# FlukeNic_UNITB.net
KiCad netlist of a schematic drawn in EAGLE
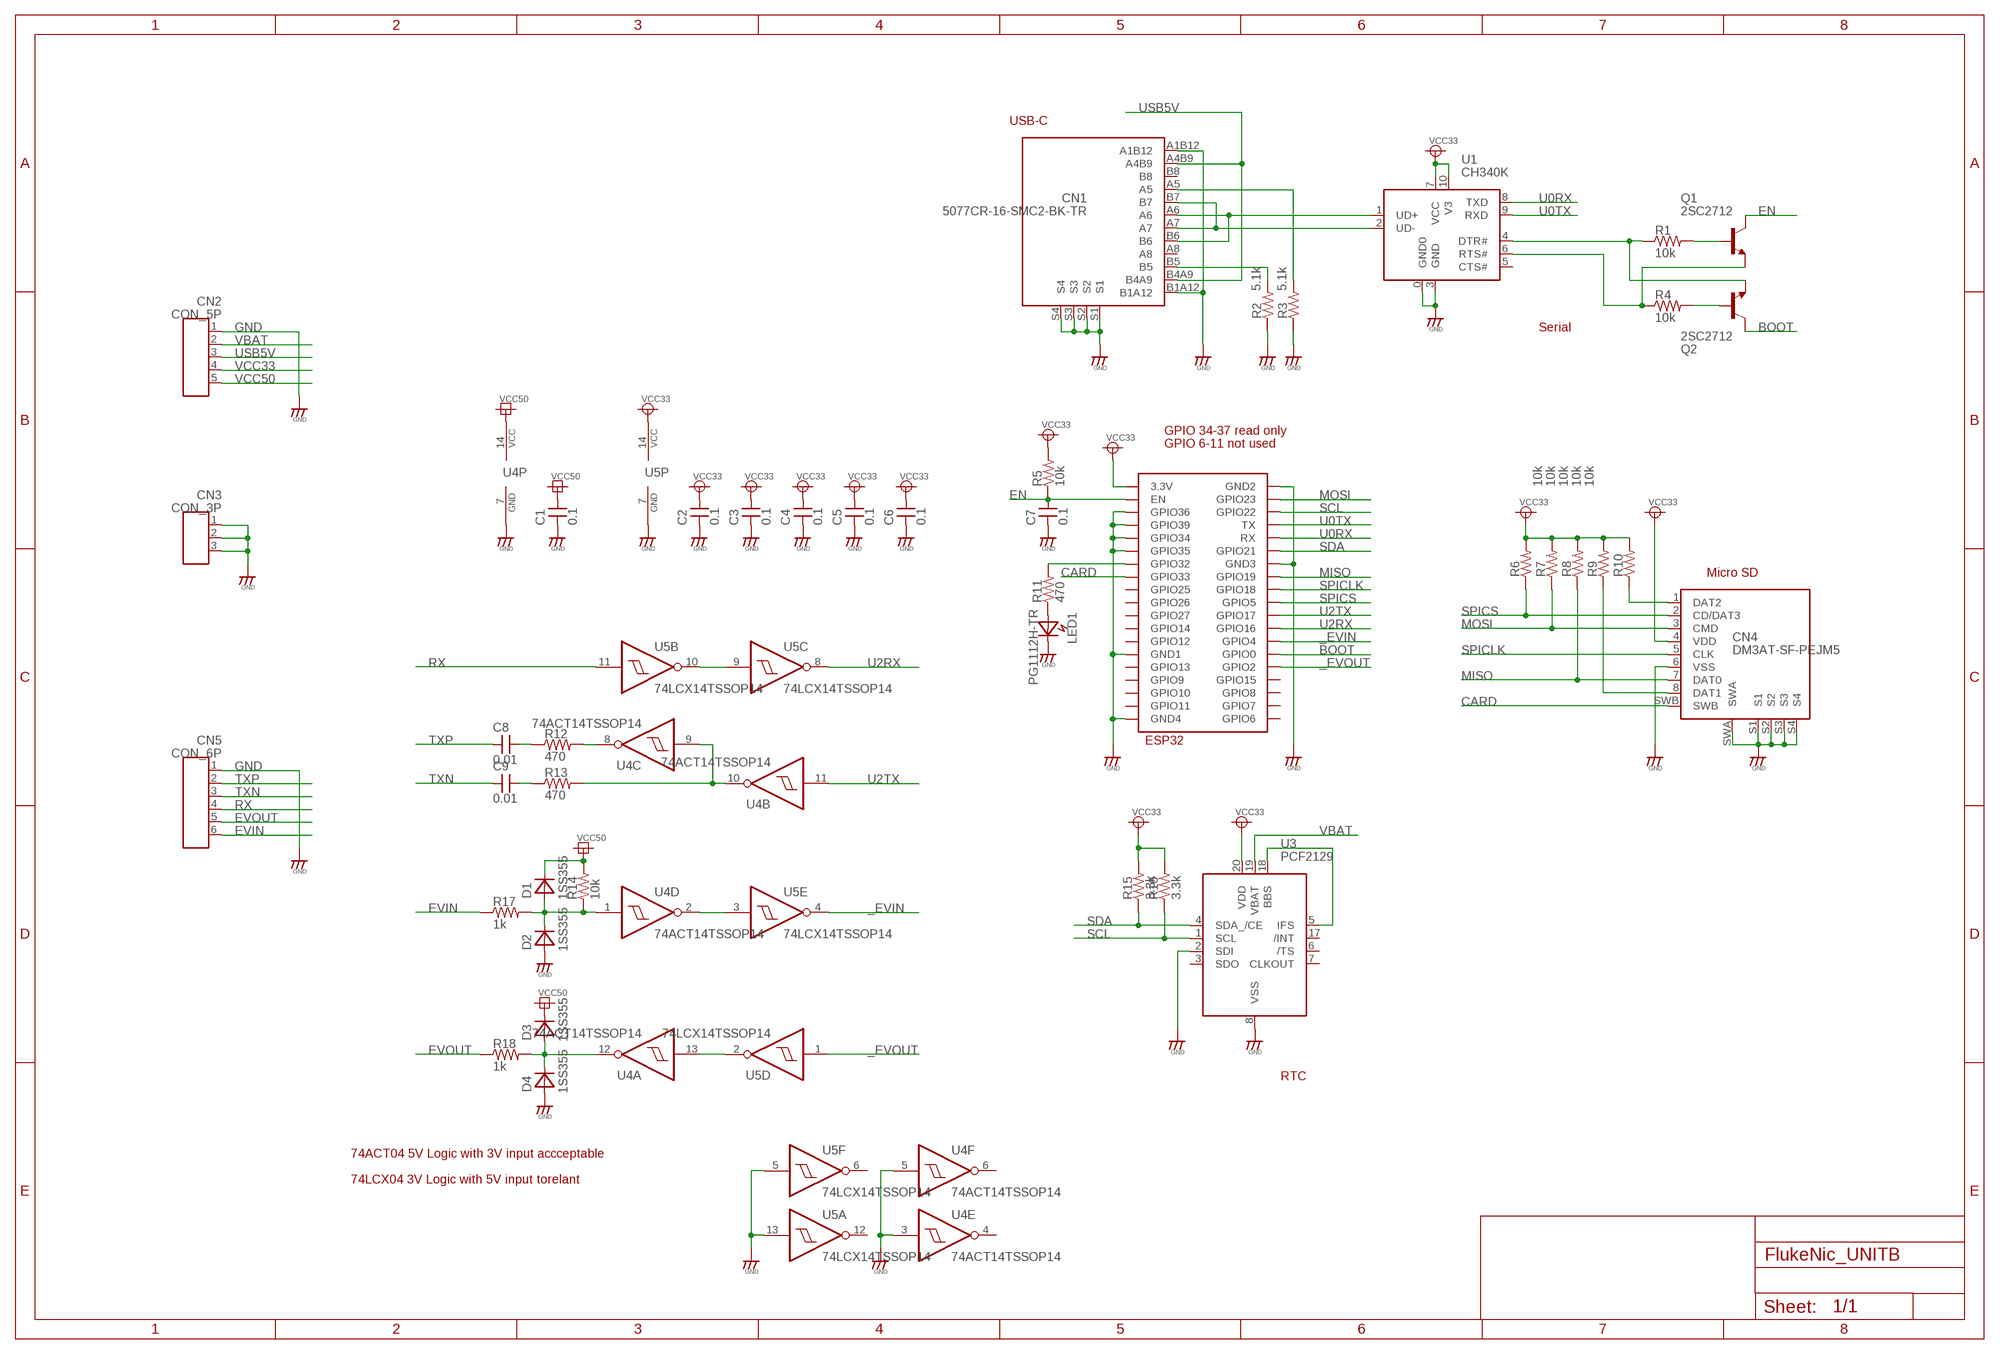
[diagram p0: schematic, sheet 1]

(export (version "E")
  (design (tool "Eeschema 10.0.6"))
  (components
    (comp (ref "C1")
      (value "0.1")
      (footprint "eagle-import:C2012")
      (libsource (lib "eagle-import") (part "CAPSM2012"))
    )
    (comp (ref "C2")
      (value "0.1")
      (footprint "eagle-import:C2012")
      (libsource (lib "eagle-import") (part "CAPSM2012"))
    )
    (comp (ref "C3")
      (value "0.1")
      (footprint "eagle-import:C2012")
      (libsource (lib "eagle-import") (part "CAPSM2012"))
    )
    (comp (ref "C4")
      (value "0.1")
      (footprint "eagle-import:C2012")
      (libsource (lib "eagle-import") (part "CAPSM2012"))
    )
    (comp (ref "C5")
      (value "0.1")
      (footprint "eagle-import:C2012")
      (libsource (lib "eagle-import") (part "CAPSM2012"))
    )
    (comp (ref "C6")
      (value "0.1")
      (footprint "eagle-import:C2012")
      (libsource (lib "eagle-import") (part "CAPSM2012"))
    )
    (comp (ref "C7")
      (value "0.1")
      (footprint "eagle-import:C2012")
      (libsource (lib "eagle-import") (part "CAPSM2012"))
    )
    (comp (ref "C8")
      (value "0.01")
      (footprint "eagle-import:C2012")
      (libsource (lib "eagle-import") (part "CAPSM2012"))
    )
    (comp (ref "C9")
      (value "0.01")
      (footprint "eagle-import:C2012")
      (libsource (lib "eagle-import") (part "CAPSM2012"))
    )
    (comp (ref "CN1")
      (value "5077CR-16-SMC2-BK-TR")
      (footprint "eagle-import:5077CR-16-SMC2-BK-TR")
      (libsource (lib "eagle-import") (part "5077CR-16-SMC2-BK-TR"))
    )
    (comp (ref "CN2")
      (value "CON_5P")
      (footprint "eagle-import:CON_HDR_SIP5")
      (libsource (lib "eagle-import") (part "CON_5P"))
    )
    (comp (ref "CN3")
      (value "CON_3P")
      (footprint "eagle-import:CON_HDR_SIP3")
      (libsource (lib "eagle-import") (part "CON_3P"))
    )
    (comp (ref "CN4")
      (value "DM3AT-SF-PEJM5")
      (footprint "eagle-import:DM3AT-SF-PEJM5")
      (libsource (lib "eagle-import") (part "DM3AT-SF-PEJM5"))
    )
    (comp (ref "CN5")
      (value "CON_6P")
      (footprint "eagle-import:CON_HDR_SIP6")
      (libsource (lib "eagle-import") (part "CON_6P"))
    )
    (comp (ref "D1")
      (value "1SS355")
      (footprint "eagle-import:SOD323")
      (libsource (lib "eagle-import") (part "DIODESOD323"))
    )
    (comp (ref "D2")
      (value "1SS355")
      (footprint "eagle-import:SOD323")
      (libsource (lib "eagle-import") (part "DIODESOD323"))
    )
    (comp (ref "D3")
      (value "1SS355")
      (footprint "eagle-import:SOD323")
      (libsource (lib "eagle-import") (part "DIODESOD323"))
    )
    (comp (ref "D4")
      (value "1SS355")
      (footprint "eagle-import:SOD323")
      (libsource (lib "eagle-import") (part "DIODESOD323"))
    )
    (comp (ref "LED1")
      (value "PG1112H-TR")
      (footprint "eagle-import:LED2125")
      (libsource (lib "eagle-import") (part "LED2125"))
    )
    (comp (ref "Q1")
      (value "2SC2712")
      (footprint "eagle-import:SC59")
      (libsource (lib "eagle-import") (part "2SC2712"))
    )
    (comp (ref "Q2")
      (value "2SC2712")
      (footprint "eagle-import:SC59")
      (libsource (lib "eagle-import") (part "2SC2712"))
    )
    (comp (ref "R1")
      (value "10k")
      (footprint "eagle-import:R2012")
      (libsource (lib "eagle-import") (part "RSMD2012"))
    )
    (comp (ref "R2")
      (value "5.1k")
      (footprint "eagle-import:R2012")
      (libsource (lib "eagle-import") (part "RSMD2012"))
    )
    (comp (ref "R3")
      (value "5.1k")
      (footprint "eagle-import:R2012")
      (libsource (lib "eagle-import") (part "RSMD2012"))
    )
    (comp (ref "R4")
      (value "10k")
      (footprint "eagle-import:R2012")
      (libsource (lib "eagle-import") (part "RSMD2012"))
    )
    (comp (ref "R5")
      (value "10k")
      (footprint "eagle-import:R2012")
      (libsource (lib "eagle-import") (part "RSMD2012"))
    )
    (comp (ref "R6")
      (value "10k")
      (footprint "eagle-import:R2012")
      (libsource (lib "eagle-import") (part "RSMD2012"))
    )
    (comp (ref "R7")
      (value "10k")
      (footprint "eagle-import:R2012")
      (libsource (lib "eagle-import") (part "RSMD2012"))
    )
    (comp (ref "R8")
      (value "10k")
      (footprint "eagle-import:R2012")
      (libsource (lib "eagle-import") (part "RSMD2012"))
    )
    (comp (ref "R9")
      (value "10k")
      (footprint "eagle-import:R2012")
      (libsource (lib "eagle-import") (part "RSMD2012"))
    )
    (comp (ref "R10")
      (value "10k")
      (footprint "eagle-import:R2012")
      (libsource (lib "eagle-import") (part "RSMD2012"))
    )
    (comp (ref "R11")
      (value "470")
      (footprint "eagle-import:R2012")
      (libsource (lib "eagle-import") (part "RSMD2012"))
    )
    (comp (ref "R12")
      (value "470")
      (footprint "eagle-import:R2012")
      (libsource (lib "eagle-import") (part "RSMD2012"))
    )
    (comp (ref "R13")
      (value "470")
      (footprint "eagle-import:R2012")
      (libsource (lib "eagle-import") (part "RSMD2012"))
    )
    (comp (ref "R14")
      (value "10k")
      (footprint "eagle-import:R2012")
      (libsource (lib "eagle-import") (part "RSMD2012"))
    )
    (comp (ref "R15")
      (value "3.3k")
      (footprint "eagle-import:R2012")
      (libsource (lib "eagle-import") (part "RSMD2012"))
    )
    (comp (ref "R16")
      (value "3.3k")
      (footprint "eagle-import:R2012")
      (libsource (lib "eagle-import") (part "RSMD2012"))
    )
    (comp (ref "R17")
      (value "1k")
      (footprint "eagle-import:R2012")
      (libsource (lib "eagle-import") (part "RSMD2012"))
    )
    (comp (ref "R18")
      (value "1k")
      (footprint "eagle-import:R2012")
      (libsource (lib "eagle-import") (part "RSMD2012"))
    )
    (comp (ref "U1")
      (value "CH340K")
      (footprint "eagle-import:ESSOP10")
      (libsource (lib "eagle-import") (part "CH340K"))
    )
    (comp (ref "U2")
      (value "ESP32-WROOM")
      (footprint "eagle-import:ESP32-WROOM")
      (libsource (lib "eagle-import") (part "ESP32-WROOM"))
    )
    (comp (ref "U3")
      (value "PCF2129")
      (footprint "eagle-import:SO20")
      (libsource (lib "eagle-import") (part "PCF2129"))
    )
    (comp (ref "U4")
      (value "74ACT14TSSOP14")
      (footprint "eagle-import:TSSOP14")
      (libsource (lib "eagle-import") (part "7414TSSOP14VHCT"))
    )
    (comp (ref "U5")
      (value "74LCX14TSSOP14")
      (footprint "eagle-import:TSSOP14")
      (libsource (lib "eagle-import") (part "7414TSSOP14LCX"))
    )
  )
  (nets
    (net (code "1") (name "/BOOT") (class "Default")
      (node (ref "Q2") (pin "C") (pinfunction "C_C") (pintype "passive"))
      (node (ref "U2") (pin "IO0") (pinfunction "GPIO0_IO0") (pintype "bidirectional"))
    )
    (net (code "2") (name "/CARD") (class "Default")
      (node (ref "CN4") (pin "SWB") (pinfunction "SWB_SWB") (pintype "passive"))
      (node (ref "U2") (pin "IO33") (pinfunction "GPIO33_IO33") (pintype "bidirectional"))
    )
    (net (code "3") (name "/EN") (class "Default")
      (node (ref "C7") (pin "2") (pinfunction "2_2") (pintype "passive"))
      (node (ref "Q1") (pin "C") (pinfunction "C_C") (pintype "passive"))
      (node (ref "R5") (pin "1") (pinfunction "1_1") (pintype "passive"))
      (node (ref "U2") (pin "EN") (pinfunction "EN_EN") (pintype "bidirectional"))
    )
    (net (code "4") (name "/EVIN") (class "Default")
      (node (ref "CN5") (pin "6") (pinfunction "6_6") (pintype "passive"))
      (node (ref "R17") (pin "1") (pinfunction "1_1") (pintype "passive"))
    )
    (net (code "5") (name "/EVOUT") (class "Default")
      (node (ref "CN5") (pin "5") (pinfunction "5_5") (pintype "passive"))
      (node (ref "R18") (pin "1") (pinfunction "1_1") (pintype "passive"))
    )
    (net (code "6") (name "/MISO") (class "Default")
      (node (ref "CN4") (pin "7") (pinfunction "DAT0_7") (pintype "bidirectional"))
      (node (ref "R8") (pin "1") (pinfunction "1_1") (pintype "passive"))
      (node (ref "U2") (pin "IO19") (pinfunction "GPIO19_IO19") (pintype "bidirectional"))
    )
    (net (code "7") (name "/MOSI") (class "Default")
      (node (ref "CN4") (pin "3") (pinfunction "CMD_3") (pintype "bidirectional"))
      (node (ref "R7") (pin "1") (pinfunction "1_1") (pintype "passive"))
      (node (ref "U2") (pin "IO23") (pinfunction "GPIO23_IO23") (pintype "bidirectional"))
    )
    (net (code "8") (name "/RX") (class "Default")
      (node (ref "CN5") (pin "4") (pinfunction "4_4") (pintype "passive"))
      (node (ref "U5") (pin "11") (pinfunction "I_11") (pintype "input"))
    )
    (net (code "9") (name "/SCL") (class "Default")
      (node (ref "R16") (pin "1") (pinfunction "1_1") (pintype "passive"))
      (node (ref "U2") (pin "IO22") (pinfunction "GPIO22_IO22") (pintype "bidirectional"))
      (node (ref "U3") (pin "1") (pinfunction "SCL_1") (pintype "input"))
    )
    (net (code "10") (name "/SDA") (class "Default")
      (node (ref "R15") (pin "1") (pinfunction "1_1") (pintype "passive"))
      (node (ref "U2") (pin "IO21") (pinfunction "GPIO21_IO21") (pintype "bidirectional"))
      (node (ref "U3") (pin "4") (pinfunction "SDA_/CE_4") (pintype "bidirectional"))
    )
    (net (code "11") (name "/SPICLK") (class "Default")
      (node (ref "CN4") (pin "5") (pinfunction "CLK_5") (pintype "input"))
      (node (ref "U2") (pin "IO18") (pinfunction "GPIO18_IO18") (pintype "bidirectional"))
    )
    (net (code "12") (name "/SPICS") (class "Default")
      (node (ref "CN4") (pin "2") (pinfunction "CD/DAT3_2") (pintype "bidirectional"))
      (node (ref "R6") (pin "1") (pinfunction "1_1") (pintype "passive"))
      (node (ref "U2") (pin "IO5") (pinfunction "GPIO5_IO5") (pintype "bidirectional"))
    )
    (net (code "13") (name "/TXN") (class "Default")
      (node (ref "C9") (pin "1") (pinfunction "1_1") (pintype "passive"))
      (node (ref "CN5") (pin "3") (pinfunction "3_3") (pintype "passive"))
    )
    (net (code "14") (name "/TXP") (class "Default")
      (node (ref "C8") (pin "1") (pinfunction "1_1") (pintype "passive"))
      (node (ref "CN5") (pin "2") (pinfunction "2_2") (pintype "passive"))
    )
    (net (code "15") (name "/U0RX") (class "Default")
      (node (ref "U1") (pin "8") (pinfunction "TXD_8") (pintype "output"))
      (node (ref "U2") (pin "RX") (pinfunction "RX_RX") (pintype "bidirectional"))
    )
    (net (code "16") (name "/U0TX") (class "Default")
      (node (ref "U1") (pin "9") (pinfunction "RXD_9") (pintype "input"))
      (node (ref "U2") (pin "TX") (pinfunction "TX_TX") (pintype "bidirectional"))
    )
    (net (code "17") (name "/U2RX") (class "Default")
      (node (ref "U2") (pin "IO16") (pinfunction "GPIO16_IO16") (pintype "bidirectional"))
      (node (ref "U5") (pin "8") (pinfunction "O_8") (pintype "output"))
    )
    (net (code "18") (name "/U2TX") (class "Default")
      (node (ref "U2") (pin "IO17") (pinfunction "GPIO17_IO17") (pintype "bidirectional"))
      (node (ref "U4") (pin "11") (pinfunction "I_11") (pintype "input"))
    )
    (net (code "19") (name "/USB5V") (class "Default")
      (node (ref "CN1") (pin "A4B9") (pinfunction "A4B9_A4B9") (pintype "bidirectional"))
      (node (ref "CN1") (pin "B4A9") (pinfunction "B4A9_B4A9") (pintype "bidirectional"))
      (node (ref "CN2") (pin "3") (pinfunction "3_3") (pintype "passive"))
    )
    (net (code "20") (name "/VBAT") (class "Default")
      (node (ref "CN2") (pin "2") (pinfunction "2_2") (pintype "passive"))
      (node (ref "U3") (pin "19") (pinfunction "VBAT_19") (pintype "power_in"))
    )
    (net (code "21") (name "/_EVIN") (class "Default")
      (node (ref "U2") (pin "IO4") (pinfunction "GPIO4_IO4") (pintype "bidirectional"))
      (node (ref "U5") (pin "4") (pinfunction "O_4") (pintype "output"))
    )
    (net (code "22") (name "/_EVOUT") (class "Default")
      (node (ref "U2") (pin "IO2") (pinfunction "GPIO2_IO2") (pintype "bidirectional"))
      (node (ref "U5") (pin "1") (pinfunction "I_1") (pintype "input"))
    )
    (net (code "23") (name "GND") (class "Default")
      (node (ref "C1") (pin "1") (pinfunction "1_1") (pintype "passive"))
      (node (ref "C2") (pin "1") (pinfunction "1_1") (pintype "passive"))
      (node (ref "C3") (pin "1") (pinfunction "1_1") (pintype "passive"))
      (node (ref "C4") (pin "1") (pinfunction "1_1") (pintype "passive"))
      (node (ref "C5") (pin "1") (pinfunction "1_1") (pintype "passive"))
      (node (ref "C6") (pin "1") (pinfunction "1_1") (pintype "passive"))
      (node (ref "C7") (pin "1") (pinfunction "1_1") (pintype "passive"))
      (node (ref "CN1") (pin "A1B12") (pinfunction "A1B12_A1B12") (pintype "bidirectional"))
      (node (ref "CN1") (pin "B1A12") (pinfunction "B1A12_B1A12") (pintype "bidirectional"))
      (node (ref "CN1") (pin "S1") (pinfunction "S1_S1") (pintype "bidirectional"))
      (node (ref "CN1") (pin "S2") (pinfunction "S2_S2") (pintype "bidirectional"))
      (node (ref "CN1") (pin "S3") (pinfunction "S3_S3") (pintype "bidirectional"))
      (node (ref "CN1") (pin "S4") (pinfunction "S4_S4") (pintype "bidirectional"))
      (node (ref "CN2") (pin "1") (pinfunction "1_1") (pintype "passive"))
      (node (ref "CN3") (pin "1") (pinfunction "1_1") (pintype "passive"))
      (node (ref "CN3") (pin "2") (pinfunction "2_2") (pintype "passive"))
      (node (ref "CN3") (pin "3") (pinfunction "3_3") (pintype "passive"))
      (node (ref "CN4") (pin "6") (pinfunction "VSS_6") (pintype "power_in"))
      (node (ref "CN4") (pin "S1") (pinfunction "S1_S1") (pintype "power_in"))
      (node (ref "CN4") (pin "S2") (pinfunction "S2_S2") (pintype "power_in"))
      (node (ref "CN4") (pin "S3") (pinfunction "S3_S3") (pintype "power_in"))
      (node (ref "CN4") (pin "S4") (pinfunction "S4_S4") (pintype "power_in"))
      (node (ref "CN4") (pin "SWA") (pinfunction "SWA_SWA") (pintype "passive"))
      (node (ref "CN5") (pin "1") (pinfunction "1_1") (pintype "passive"))
      (node (ref "D2") (pin "1") (pinfunction "A_1") (pintype "passive"))
      (node (ref "D4") (pin "1") (pinfunction "A_1") (pintype "passive"))
      (node (ref "LED1") (pin "K") (pinfunction "K_K") (pintype "passive"))
      (node (ref "R2") (pin "1") (pinfunction "1_1") (pintype "passive"))
      (node (ref "R3") (pin "1") (pinfunction "1_1") (pintype "passive"))
      (node (ref "U1") (pin "0") (pinfunction "GND0_0") (pintype "power_in"))
      (node (ref "U1") (pin "3") (pinfunction "GND_3") (pintype "power_in"))
      (node (ref "U2") (pin "GND1") (pinfunction "GND1_GND1") (pintype "bidirectional"))
      (node (ref "U2") (pin "GND2") (pinfunction "GND2_GND2") (pintype "bidirectional"))
      (node (ref "U2") (pin "GND3") (pinfunction "GND3_GND3") (pintype "bidirectional"))
      (node (ref "U2") (pin "GND4") (pinfunction "GND4_GND4") (pintype "bidirectional"))
      (node (ref "U2") (pin "IO34") (pinfunction "GPIO34_IO34") (pintype "bidirectional"))
      (node (ref "U2") (pin "IO35") (pinfunction "GPIO35_IO35") (pintype "bidirectional"))
      (node (ref "U2") (pin "SENSOR_VN") (pinfunction "GPIO39_SENSOR_VN") (pintype "bidirectional"))
      (node (ref "U2") (pin "SENSOR_VP") (pinfunction "GPIO36_SENSOR_VP") (pintype "bidirectional"))
      (node (ref "U3") (pin "2") (pinfunction "SDI_2") (pintype "input"))
      (node (ref "U3") (pin "8") (pinfunction "VSS_8") (pintype "power_in"))
      (node (ref "U4") (pin "3") (pinfunction "I_3") (pintype "input"))
      (node (ref "U4") (pin "5") (pinfunction "I_5") (pintype "input"))
      (node (ref "U4") (pin "7") (pinfunction "GND_7") (pintype "power_in"))
      (node (ref "U5") (pin "13") (pinfunction "I_13") (pintype "input"))
      (node (ref "U5") (pin "5") (pinfunction "I_5") (pintype "input"))
      (node (ref "U5") (pin "7") (pinfunction "GND_7") (pintype "power_in"))
    )
    (net (code "24") (name "Net-(C8-Pad2)") (class "Default")
      (node (ref "C8") (pin "2") (pinfunction "2_2") (pintype "passive"))
      (node (ref "R12") (pin "1") (pinfunction "1_1") (pintype "passive"))
    )
    (net (code "25") (name "Net-(C9-Pad2)") (class "Default")
      (node (ref "C9") (pin "2") (pinfunction "2_2") (pintype "passive"))
      (node (ref "R13") (pin "1") (pinfunction "1_1") (pintype "passive"))
    )
    (net (code "26") (name "Net-(CN1-PadA5)") (class "Default")
      (node (ref "CN1") (pin "A5") (pinfunction "A5_A5") (pintype "bidirectional"))
      (node (ref "R3") (pin "2") (pinfunction "2_2") (pintype "passive"))
    )
    (net (code "27") (name "Net-(CN1-PadB5)") (class "Default")
      (node (ref "CN1") (pin "B5") (pinfunction "B5_B5") (pintype "bidirectional"))
      (node (ref "R2") (pin "2") (pinfunction "2_2") (pintype "passive"))
    )
    (net (code "28") (name "Net-(CN4-DAT1)") (class "Default")
      (node (ref "CN4") (pin "8") (pinfunction "DAT1_8") (pintype "bidirectional"))
      (node (ref "R9") (pin "1") (pinfunction "1_1") (pintype "passive"))
    )
    (net (code "29") (name "Net-(CN4-DAT2)") (class "Default")
      (node (ref "CN4") (pin "1") (pinfunction "DAT2_1") (pintype "bidirectional"))
      (node (ref "R10") (pin "1") (pinfunction "1_1") (pintype "passive"))
    )
    (net (code "30") (name "Net-(D1-A)") (class "Default")
      (node (ref "D1") (pin "1") (pinfunction "A_1") (pintype "passive"))
      (node (ref "D2") (pin "2") (pinfunction "K_2") (pintype "passive"))
      (node (ref "R14") (pin "1") (pinfunction "1_1") (pintype "passive"))
      (node (ref "R17") (pin "2") (pinfunction "2_2") (pintype "passive"))
      (node (ref "U4") (pin "1") (pinfunction "I_1") (pintype "input"))
    )
    (net (code "31") (name "Net-(D3-A)") (class "Default")
      (node (ref "D3") (pin "1") (pinfunction "A_1") (pintype "passive"))
      (node (ref "D4") (pin "2") (pinfunction "K_2") (pintype "passive"))
      (node (ref "R18") (pin "2") (pinfunction "2_2") (pintype "passive"))
      (node (ref "U4") (pin "12") (pinfunction "O_12") (pintype "output"))
    )
    (net (code "32") (name "Net-(LED1-PadA)") (class "Default")
      (node (ref "LED1") (pin "A") (pinfunction "A_A") (pintype "passive"))
      (node (ref "R11") (pin "1") (pinfunction "1_1") (pintype "passive"))
    )
    (net (code "33") (name "Net-(Q1-PadB)") (class "Default")
      (node (ref "Q1") (pin "B") (pinfunction "B_B") (pintype "passive"))
      (node (ref "R1") (pin "2") (pinfunction "2_2") (pintype "passive"))
    )
    (net (code "34") (name "Net-(Q2-PadB)") (class "Default")
      (node (ref "Q2") (pin "B") (pinfunction "B_B") (pintype "passive"))
      (node (ref "R4") (pin "2") (pinfunction "2_2") (pintype "passive"))
    )
    (net (code "35") (name "Net-(U1-DTR#)") (class "Default")
      (node (ref "Q2") (pin "E") (pinfunction "E_E") (pintype "passive"))
      (node (ref "R1") (pin "1") (pinfunction "1_1") (pintype "passive"))
      (node (ref "U1") (pin "4") (pinfunction "DTR#_4") (pintype "output"))
    )
    (net (code "36") (name "Net-(U1-RTS#)") (class "Default")
      (node (ref "Q1") (pin "E") (pinfunction "E_E") (pintype "passive"))
      (node (ref "R4") (pin "1") (pinfunction "1_1") (pintype "passive"))
      (node (ref "U1") (pin "6") (pinfunction "RTS#_6") (pintype "output"))
    )
    (net (code "37") (name "Net-(U1-UD+)") (class "Default")
      (node (ref "CN1") (pin "A6") (pinfunction "A6_A6") (pintype "bidirectional"))
      (node (ref "CN1") (pin "B6") (pinfunction "B6_B6") (pintype "bidirectional"))
      (node (ref "U1") (pin "1") (pinfunction "UD+_1") (pintype "bidirectional"))
    )
    (net (code "38") (name "Net-(U1-UD-)") (class "Default")
      (node (ref "CN1") (pin "A7") (pinfunction "A7_A7") (pintype "bidirectional"))
      (node (ref "CN1") (pin "B7") (pinfunction "B7_B7") (pintype "bidirectional"))
      (node (ref "U1") (pin "2") (pinfunction "UD-_2") (pintype "bidirectional"))
    )
    (net (code "39") (name "Net-(U2-GPIO32)") (class "Default")
      (node (ref "R11") (pin "2") (pinfunction "2_2") (pintype "passive"))
      (node (ref "U2") (pin "IO32") (pinfunction "GPIO32_IO32") (pintype "bidirectional"))
    )
    (net (code "40") (name "Net-(U3-BBS)") (class "Default")
      (node (ref "U3") (pin "18") (pinfunction "BBS_18") (pintype "power_in"))
      (node (ref "U3") (pin "5") (pinfunction "IFS_5") (pintype "input"))
    )
    (net (code "41") (name "Net-(U4A-I)") (class "Default")
      (node (ref "U4") (pin "13") (pinfunction "I_13") (pintype "input"))
      (node (ref "U5") (pin "2") (pinfunction "O_2") (pintype "output"))
    )
    (net (code "42") (name "Net-(U4B-O)") (class "Default")
      (node (ref "R13") (pin "2") (pinfunction "2_2") (pintype "passive"))
      (node (ref "U4") (pin "10") (pinfunction "O_10") (pintype "output"))
      (node (ref "U4") (pin "9") (pinfunction "I_9") (pintype "input"))
    )
    (net (code "43") (name "Net-(U4C-O)") (class "Default")
      (node (ref "R12") (pin "2") (pinfunction "2_2") (pintype "passive"))
      (node (ref "U4") (pin "8") (pinfunction "O_8") (pintype "output"))
    )
    (net (code "44") (name "Net-(U4D-O)") (class "Default")
      (node (ref "U4") (pin "2") (pinfunction "O_2") (pintype "output"))
      (node (ref "U5") (pin "3") (pinfunction "I_3") (pintype "input"))
    )
    (net (code "45") (name "Net-(U5B-O)") (class "Default")
      (node (ref "U5") (pin "10") (pinfunction "O_10") (pintype "output"))
      (node (ref "U5") (pin "9") (pinfunction "I_9") (pintype "input"))
    )
    (net (code "46") (name "VCC33") (class "Default")
      (node (ref "C2") (pin "2") (pinfunction "2_2") (pintype "passive"))
      (node (ref "C3") (pin "2") (pinfunction "2_2") (pintype "passive"))
      (node (ref "C4") (pin "2") (pinfunction "2_2") (pintype "passive"))
      (node (ref "C5") (pin "2") (pinfunction "2_2") (pintype "passive"))
      (node (ref "C6") (pin "2") (pinfunction "2_2") (pintype "passive"))
      (node (ref "CN2") (pin "4") (pinfunction "4_4") (pintype "passive"))
      (node (ref "CN4") (pin "4") (pinfunction "VDD_4") (pintype "power_in"))
      (node (ref "R10") (pin "2") (pinfunction "2_2") (pintype "passive"))
      (node (ref "R15") (pin "2") (pinfunction "2_2") (pintype "passive"))
      (node (ref "R16") (pin "2") (pinfunction "2_2") (pintype "passive"))
      (node (ref "R5") (pin "2") (pinfunction "2_2") (pintype "passive"))
      (node (ref "R6") (pin "2") (pinfunction "2_2") (pintype "passive"))
      (node (ref "R7") (pin "2") (pinfunction "2_2") (pintype "passive"))
      (node (ref "R8") (pin "2") (pinfunction "2_2") (pintype "passive"))
      (node (ref "R9") (pin "2") (pinfunction "2_2") (pintype "passive"))
      (node (ref "U1") (pin "10") (pinfunction "V3_10") (pintype "power_in"))
      (node (ref "U1") (pin "7") (pinfunction "VCC_7") (pintype "power_in"))
      (node (ref "U2") (pin "3V3") (pinfunction "3.3V_3V3") (pintype "bidirectional"))
      (node (ref "U3") (pin "20") (pinfunction "VDD_20") (pintype "power_in"))
      (node (ref "U5") (pin "14") (pinfunction "VCC_14") (pintype "power_in"))
    )
    (net (code "47") (name "VCC50") (class "Default")
      (node (ref "C1") (pin "2") (pinfunction "2_2") (pintype "passive"))
      (node (ref "CN2") (pin "5") (pinfunction "5_5") (pintype "passive"))
      (node (ref "D1") (pin "2") (pinfunction "K_2") (pintype "passive"))
      (node (ref "D3") (pin "2") (pinfunction "K_2") (pintype "passive"))
      (node (ref "R14") (pin "2") (pinfunction "2_2") (pintype "passive"))
      (node (ref "U4") (pin "14") (pinfunction "VCC_14") (pintype "power_in"))
    )
    (net (code "48") (name "unconnected-(CN1-PadA8)") (class "Default")
      (node (ref "CN1") (pin "A8") (pinfunction "A8_A8") (pintype "bidirectional"))
    )
    (net (code "49") (name "unconnected-(CN1-PadB8)") (class "Default")
      (node (ref "CN1") (pin "B8") (pinfunction "B8_B8") (pintype "bidirectional"))
    )
    (net (code "50") (name "unconnected-(U1-CTS#-Pad5)") (class "Default")
      (node (ref "U1") (pin "5") (pinfunction "CTS#_5") (pintype "input"))
    )
    (net (code "51") (name "unconnected-(U2-GPIO6-PadCLK)") (class "Default")
      (node (ref "U2") (pin "CLK") (pinfunction "GPIO6_CLK") (pintype "bidirectional"))
    )
    (net (code "52") (name "unconnected-(U2-GPIO7-PadSD0)") (class "Default")
      (node (ref "U2") (pin "SD0") (pinfunction "GPIO7_SD0") (pintype "bidirectional"))
    )
    (net (code "53") (name "unconnected-(U2-GPIO8-PadSD1)") (class "Default")
      (node (ref "U2") (pin "SD1") (pinfunction "GPIO8_SD1") (pintype "bidirectional"))
    )
    (net (code "54") (name "unconnected-(U2-GPIO9-PadSD2)") (class "Default")
      (node (ref "U2") (pin "SD2") (pinfunction "GPIO9_SD2") (pintype "bidirectional"))
    )
    (net (code "55") (name "unconnected-(U2-GPIO10-PadSD3)") (class "Default")
      (node (ref "U2") (pin "SD3") (pinfunction "GPIO10_SD3") (pintype "bidirectional"))
    )
    (net (code "56") (name "unconnected-(U2-GPIO11-PadCMD)") (class "Default")
      (node (ref "U2") (pin "CMD") (pinfunction "GPIO11_CMD") (pintype "bidirectional"))
    )
    (net (code "57") (name "unconnected-(U2-GPIO12-PadIO12)") (class "Default")
      (node (ref "U2") (pin "IO12") (pinfunction "GPIO12_IO12") (pintype "bidirectional"))
    )
    (net (code "58") (name "unconnected-(U2-GPIO13-PadIO13)") (class "Default")
      (node (ref "U2") (pin "IO13") (pinfunction "GPIO13_IO13") (pintype "bidirectional"))
    )
    (net (code "59") (name "unconnected-(U2-GPIO14-PadIO14)") (class "Default")
      (node (ref "U2") (pin "IO14") (pinfunction "GPIO14_IO14") (pintype "bidirectional"))
    )
    (net (code "60") (name "unconnected-(U2-GPIO15-PadIO15)") (class "Default")
      (node (ref "U2") (pin "IO15") (pinfunction "GPIO15_IO15") (pintype "bidirectional"))
    )
    (net (code "61") (name "unconnected-(U2-GPIO25-PadIO25)") (class "Default")
      (node (ref "U2") (pin "IO25") (pinfunction "GPIO25_IO25") (pintype "bidirectional"))
    )
    (net (code "62") (name "unconnected-(U2-GPIO26-PadIO26)") (class "Default")
      (node (ref "U2") (pin "IO26") (pinfunction "GPIO26_IO26") (pintype "bidirectional"))
    )
    (net (code "63") (name "unconnected-(U2-GPIO27-PadIO27)") (class "Default")
      (node (ref "U2") (pin "IO27") (pinfunction "GPIO27_IO27") (pintype "bidirectional"))
    )
    (net (code "64") (name "unconnected-(U3-CLKOUT-Pad7)") (class "Default")
      (node (ref "U3") (pin "7") (pinfunction "CLKOUT_7") (pintype "output"))
    )
    (net (code "65") (name "unconnected-(U3-SDO-Pad3)") (class "Default")
      (node (ref "U3") (pin "3") (pinfunction "SDO_3") (pintype "output"))
    )
    (net (code "66") (name "unconnected-(U3-{slash}INT-Pad17)") (class "Default")
      (node (ref "U3") (pin "17") (pinfunction "/INT_17") (pintype "output"))
    )
    (net (code "67") (name "unconnected-(U3-{slash}TS-Pad6)") (class "Default")
      (node (ref "U3") (pin "6") (pinfunction "/TS_6") (pintype "input"))
    )
    (net (code "68") (name "unconnected-(U4E-O-Pad4)") (class "Default")
      (node (ref "U4") (pin "4") (pinfunction "O_4") (pintype "output"))
    )
    (net (code "69") (name "unconnected-(U4F-O-Pad6)") (class "Default")
      (node (ref "U4") (pin "6") (pinfunction "O_6") (pintype "output"))
    )
    (net (code "70") (name "unconnected-(U5A-O-Pad12)") (class "Default")
      (node (ref "U5") (pin "12") (pinfunction "O_12") (pintype "output"))
    )
    (net (code "71") (name "unconnected-(U5F-O-Pad6)") (class "Default")
      (node (ref "U5") (pin "6") (pinfunction "O_6") (pintype "output"))
    )
  )
)
